# f1042.net
KiCad netlist of a schematic drawn in EAGLE
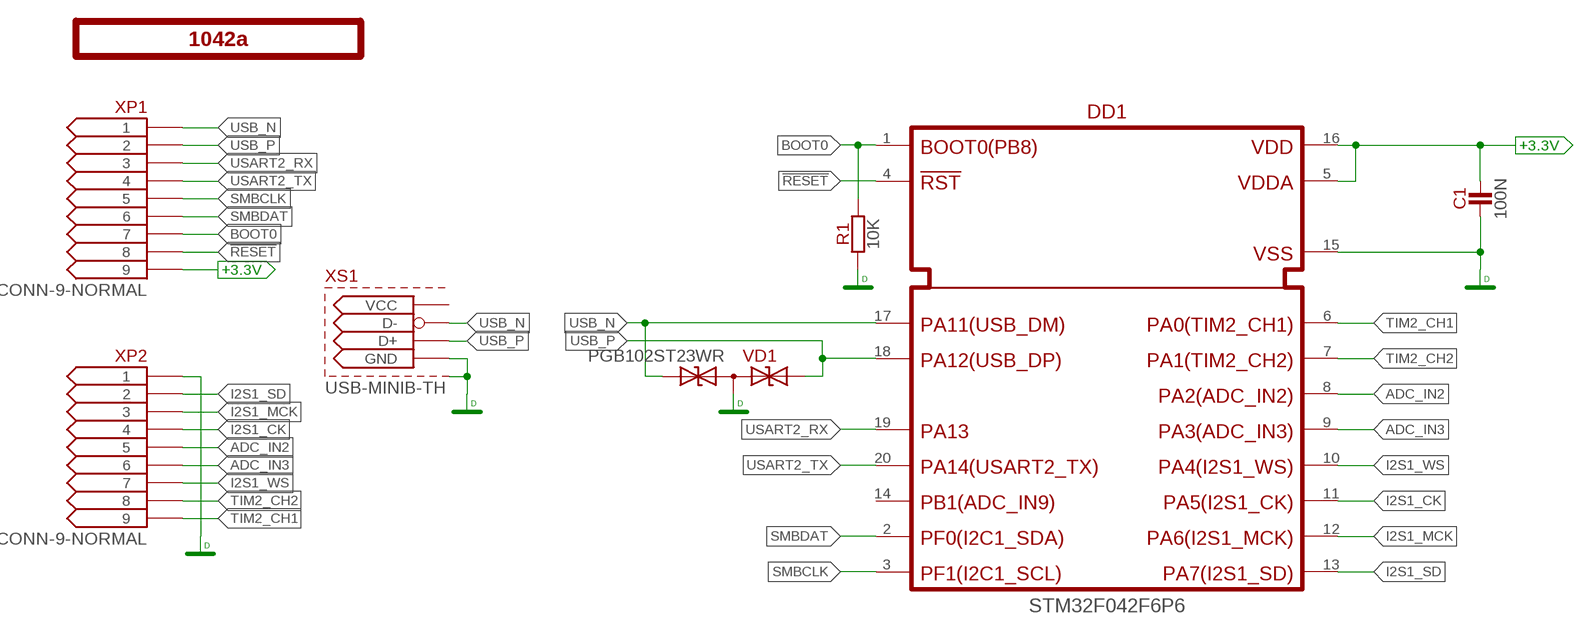
[diagram p0: schematic, sheet 1]

(export (version "E")
  (design (tool "Eeschema 10.0.6"))
  (components
    (comp (ref "C1")
      (value "100N")
      (footprint "eagle-import:C-0805")
      (libsource (lib "eagle-import") (part "?100N"))
    )
    (comp (ref "DD1")
      (value "STM32F042F6P6")
      (footprint "eagle-import:TSSOP20")
      (libsource (lib "eagle-import") (part "STM32F042F6P6"))
    )
    (comp (ref "PCB1")
      (value "1042a")
      (footprint "eagle-import:F-LOGO")
      (libsource (lib "eagle-import") (part "GENERIC-LOGO"))
    )
    (comp (ref "R1")
      (value "10K")
      (footprint "eagle-import:R-0805")
      (libsource (lib "eagle-import") (part "?10K"))
    )
    (comp (ref "VD1")
      (value "PGB102ST23WR")
      (footprint "eagle-import:SOT23")
      (libsource (lib "eagle-import") (part "PGB102ST23WR"))
    )
    (comp (ref "XP1")
      (value "CONN-9-NORMAL")
      (footprint "eagle-import:MA03-9")
      (libsource (lib "eagle-import") (part "CONN-9-?NORMAL"))
    )
    (comp (ref "XP2")
      (value "CONN-9-NORMAL")
      (footprint "eagle-import:MA03-9")
      (libsource (lib "eagle-import") (part "CONN-9-?NORMAL"))
    )
    (comp (ref "XS1")
      (value "USB-MINIB-TH")
      (footprint "eagle-import:USB-MB-H")
      (libsource (lib "eagle-import") (part "USB-MINIB-TH"))
    )
  )
  (nets
    (net (code "1") (name "+3.3V") (class "Default")
      (node (ref "C1") (pin "2") (pinfunction "2_2") (pintype "passive"))
      (node (ref "DD1") (pin "16") (pinfunction "VDD_16") (pintype "input"))
      (node (ref "DD1") (pin "5") (pinfunction "VDDA_5") (pintype "input"))
      (node (ref "XP1") (pin "9") (pinfunction "9_9") (pintype "passive"))
    )
    (net (code "2") (name "/~{RESET}") (class "Default")
      (node (ref "DD1") (pin "4") (pinfunction "~{RST}_4") (pintype "input"))
      (node (ref "XP1") (pin "8") (pinfunction "8_8") (pintype "passive"))
    )
    (net (code "3") (name "ADC_IN2") (class "Default")
      (node (ref "DD1") (pin "8") (pinfunction "PA2_8") (pintype "input"))
      (node (ref "XP2") (pin "5") (pinfunction "5_5") (pintype "passive"))
    )
    (net (code "4") (name "ADC_IN3") (class "Default")
      (node (ref "DD1") (pin "9") (pinfunction "PA3_9") (pintype "input"))
      (node (ref "XP2") (pin "6") (pinfunction "6_6") (pintype "passive"))
    )
    (net (code "5") (name "BOOT0") (class "Default")
      (node (ref "DD1") (pin "1") (pinfunction "BOOT0_1") (pintype "input"))
      (node (ref "R1") (pin "2") (pinfunction "2_2") (pintype "passive"))
      (node (ref "XP1") (pin "7") (pinfunction "7_7") (pintype "passive"))
    )
    (net (code "6") (name "DGND") (class "Default")
      (node (ref "C1") (pin "1") (pinfunction "1_1") (pintype "passive"))
      (node (ref "DD1") (pin "15") (pinfunction "VSS_15") (pintype "input"))
      (node (ref "R1") (pin "1") (pinfunction "1_1") (pintype "passive"))
      (node (ref "VD1") (pin "3") (pinfunction "C_3") (pintype "passive"))
      (node (ref "XP2") (pin "1") (pinfunction "1_1") (pintype "passive"))
      (node (ref "XS1") (pin "GND") (pinfunction "GND_GND") (pintype "passive"))
      (node (ref "XS1") (pin "P$1") (pinfunction "S1_P$1") (pintype "passive"))
      (node (ref "XS1") (pin "P$2") (pinfunction "S1_P$2") (pintype "passive"))
      (node (ref "XS1") (pin "P$6") (pinfunction "S1_P$6") (pintype "passive"))
      (node (ref "XS1") (pin "P$7") (pinfunction "S1_P$7") (pintype "passive"))
    )
    (net (code "7") (name "I2S1_CK") (class "Default")
      (node (ref "DD1") (pin "11") (pinfunction "PA5_11") (pintype "input"))
      (node (ref "XP2") (pin "4") (pinfunction "4_4") (pintype "passive"))
    )
    (net (code "8") (name "I2S1_MCK") (class "Default")
      (node (ref "DD1") (pin "12") (pinfunction "PA6_12") (pintype "input"))
      (node (ref "XP2") (pin "3") (pinfunction "3_3") (pintype "passive"))
    )
    (net (code "9") (name "I2S1_SD") (class "Default")
      (node (ref "DD1") (pin "13") (pinfunction "PA7_13") (pintype "input"))
      (node (ref "XP2") (pin "2") (pinfunction "2_2") (pintype "passive"))
    )
    (net (code "10") (name "I2S1_WS") (class "Default")
      (node (ref "DD1") (pin "10") (pinfunction "PA4_10") (pintype "input"))
      (node (ref "XP2") (pin "7") (pinfunction "7_7") (pintype "passive"))
    )
    (net (code "11") (name "SMBCLK") (class "Default")
      (node (ref "DD1") (pin "3") (pinfunction "PF1_3") (pintype "input"))
      (node (ref "XP1") (pin "5") (pinfunction "5_5") (pintype "passive"))
    )
    (net (code "12") (name "SMBDAT") (class "Default")
      (node (ref "DD1") (pin "2") (pinfunction "PF0_2") (pintype "input"))
      (node (ref "XP1") (pin "6") (pinfunction "6_6") (pintype "passive"))
    )
    (net (code "13") (name "TIM2_CH1") (class "Default")
      (node (ref "DD1") (pin "6") (pinfunction "PA0_6") (pintype "input"))
      (node (ref "XP2") (pin "9") (pinfunction "9_9") (pintype "passive"))
    )
    (net (code "14") (name "TIM2_CH2") (class "Default")
      (node (ref "DD1") (pin "7") (pinfunction "PA1_7") (pintype "input"))
      (node (ref "XP2") (pin "8") (pinfunction "8_8") (pintype "passive"))
    )
    (net (code "15") (name "USART2_RX") (class "Default")
      (node (ref "DD1") (pin "19") (pinfunction "PA13_19") (pintype "input"))
      (node (ref "XP1") (pin "3") (pinfunction "3_3") (pintype "passive"))
    )
    (net (code "16") (name "USART2_TX") (class "Default")
      (node (ref "DD1") (pin "20") (pinfunction "PA14_20") (pintype "input"))
      (node (ref "XP1") (pin "4") (pinfunction "4_4") (pintype "passive"))
    )
    (net (code "17") (name "USB_N") (class "Default")
      (node (ref "DD1") (pin "17") (pinfunction "PA11_17") (pintype "input"))
      (node (ref "VD1") (pin "2") (pinfunction "A1_2") (pintype "passive"))
      (node (ref "XP1") (pin "1") (pinfunction "1_1") (pintype "passive"))
      (node (ref "XS1") (pin "D-") (pinfunction "D-_D-") (pintype "bidirectional"))
    )
    (net (code "18") (name "USB_P") (class "Default")
      (node (ref "DD1") (pin "18") (pinfunction "PA12_18") (pintype "input"))
      (node (ref "VD1") (pin "1") (pinfunction "A_1") (pintype "passive"))
      (node (ref "XP1") (pin "2") (pinfunction "2_2") (pintype "passive"))
      (node (ref "XS1") (pin "D+") (pinfunction "D+_D+") (pintype "bidirectional"))
    )
    (net (code "19") (name "unconnected-(DD1-PB1-Pad14)") (class "Default")
      (node (ref "DD1") (pin "14") (pinfunction "PB1_14") (pintype "input"))
    )
    (net (code "20") (name "unconnected-(XS1-VCC-PadVBUS)") (class "Default")
      (node (ref "XS1") (pin "VBUS") (pinfunction "VCC_VBUS") (pintype "passive"))
    )
  )
)
